# connector_board.net
KiCad netlist of a schematic drawn in EAGLE
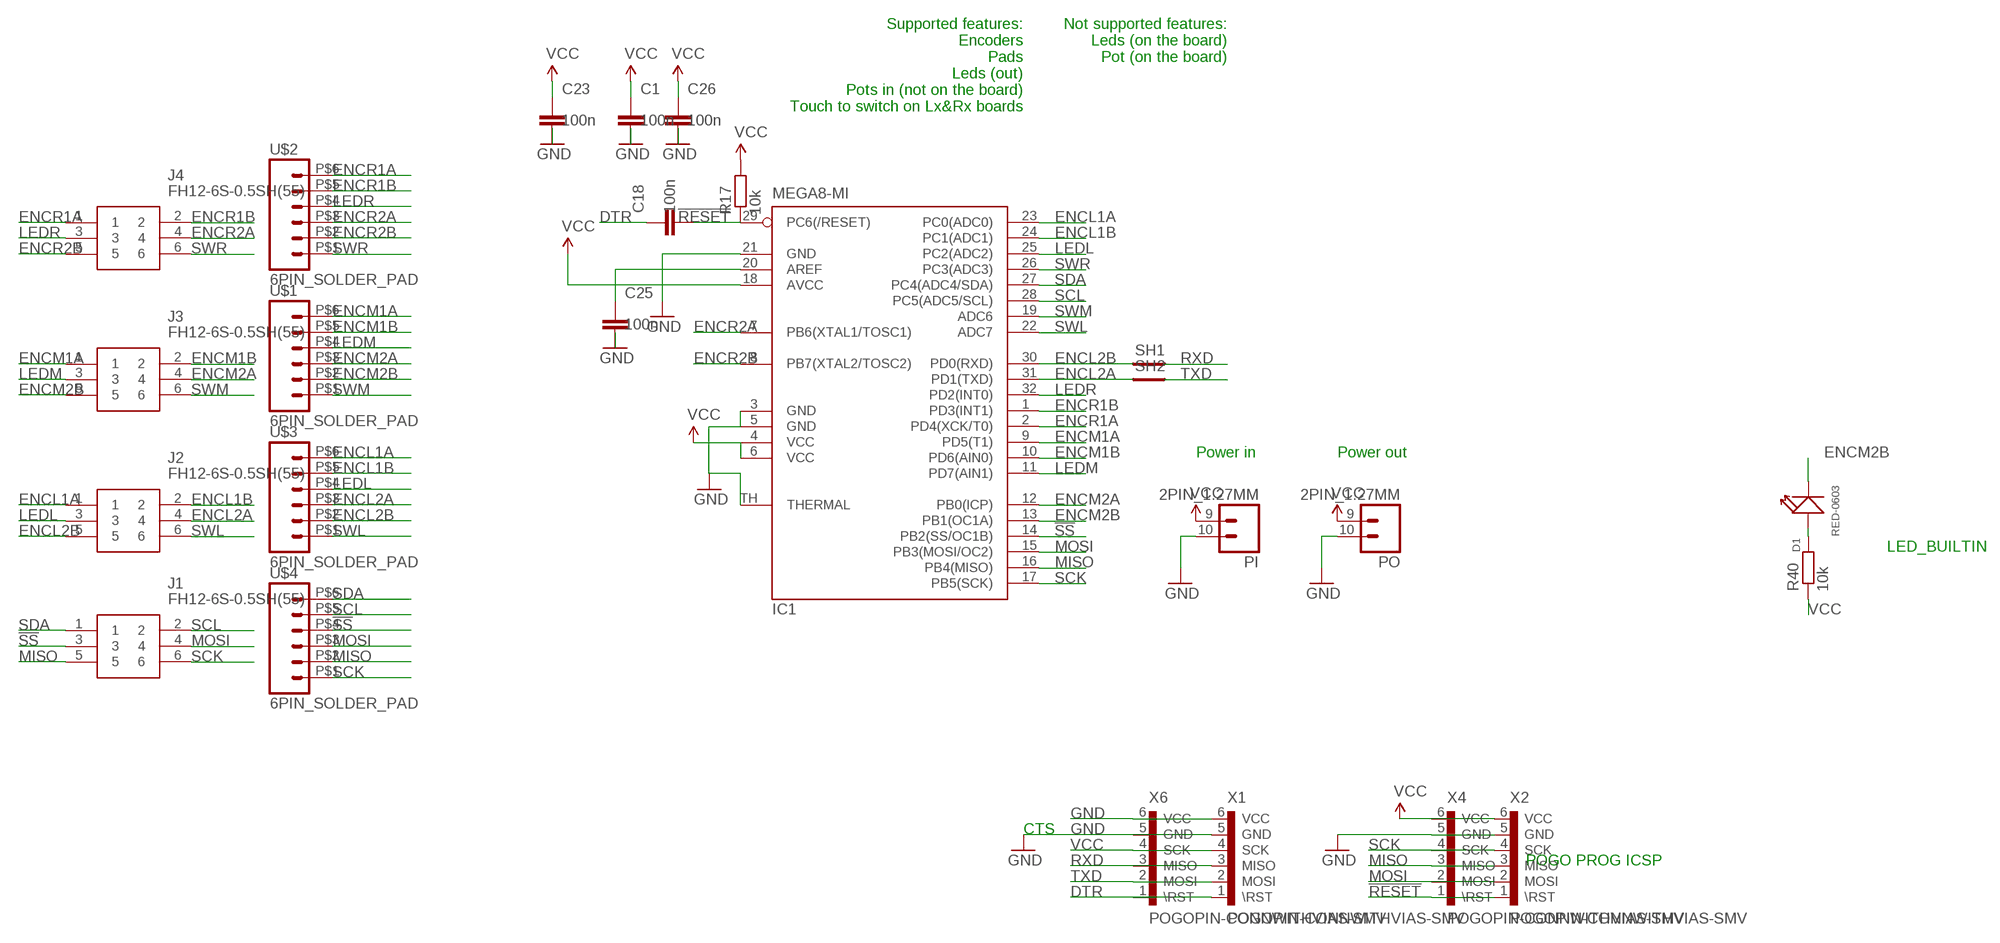
[diagram p0: schematic, sheet 1]
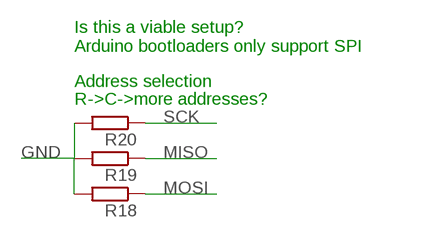
[diagram p1: schematic, sheet 2]

(export (version "E")
  (design (tool "Eeschema 10.0.6"))
  (components
    (comp (ref "C1")
      (value "100n")
      (footprint "eagle-import:C0603")
      (libsource (lib "eagle-import") (part "C-EUC0603"))
    )
    (comp (ref "C18")
      (value "100n")
      (footprint "eagle-import:C0603")
      (libsource (lib "eagle-import") (part "C-EUC0603"))
    )
    (comp (ref "C23")
      (value "100n")
      (footprint "eagle-import:C0603")
      (libsource (lib "eagle-import") (part "C-EUC0603"))
    )
    (comp (ref "C25")
      (value "100n")
      (footprint "eagle-import:C0603")
      (libsource (lib "eagle-import") (part "C-EUC0603"))
    )
    (comp (ref "C26")
      (value "100n")
      (footprint "eagle-import:C0603")
      (libsource (lib "eagle-import") (part "C-EUC0603"))
    )
    (comp (ref "D1")
      (value "RED-0603")
      (footprint "eagle-import:LED-0603")
      (fields (field (name "MPN") "19-217-R6C-AL1M2VY-3T"))
      (libsource (lib "eagle-import") (part "LED-SMD-RED-DIFFUSED(0603)"))
    )
    (comp (ref "IC1")
      (value "MEGA8-MI")
      (footprint "eagle-import:MLF32-TH")
      (fields (field (name "MPN") "ATMEGA88PA-MU"))
      (libsource (lib "eagle-import") (part "MEGA8-MI"))
    )
    (comp (ref "J1")
      (value "FH12-6S-0.5SH(55)")
      (footprint "eagle-import:FH12-6S-0.5SH(55)_1")
      (fields
        (field (name "MOUSER_PART_NUMBER") "798-FH12-6S-0.5SH55")
        (field (name "RS_PART_NUMBER") "7388811P")
      )
      (libsource (lib "eagle-import") (part "FH12-6S-0.5SH(55)"))
    )
    (comp (ref "J2")
      (value "FH12-6S-0.5SH(55)")
      (footprint "eagle-import:FH12-6S-0.5SH(55)_1")
      (fields
        (field (name "MOUSER_PART_NUMBER") "798-FH12-6S-0.5SH55")
        (field (name "RS_PART_NUMBER") "7388811P")
      )
      (libsource (lib "eagle-import") (part "FH12-6S-0.5SH(55)"))
    )
    (comp (ref "J3")
      (value "FH12-6S-0.5SH(55)")
      (footprint "eagle-import:FH12-6S-0.5SH(55)_1")
      (fields
        (field (name "MOUSER_PART_NUMBER") "798-FH12-6S-0.5SH55")
        (field (name "RS_PART_NUMBER") "7388811P")
      )
      (libsource (lib "eagle-import") (part "FH12-6S-0.5SH(55)"))
    )
    (comp (ref "J4")
      (value "FH12-6S-0.5SH(55)")
      (footprint "eagle-import:FH12-6S-0.5SH(55)_1")
      (fields
        (field (name "MOUSER_PART_NUMBER") "798-FH12-6S-0.5SH55")
        (field (name "RS_PART_NUMBER") "7388811P")
      )
      (libsource (lib "eagle-import") (part "FH12-6S-0.5SH(55)"))
    )
    (comp (ref "PI")
      (value "2PIN_1.27MM")
      (footprint "eagle-import:1X02_1.27MM_NO_SILK")
      (libsource (lib "eagle-import") (part "2PIN_1.27MM"))
    )
    (comp (ref "PO")
      (value "2PIN_1.27MM")
      (footprint "eagle-import:1X02_1.27MM_NO_SILK")
      (libsource (lib "eagle-import") (part "2PIN_1.27MM"))
    )
    (comp (ref "R17")
      (value "10k")
      (footprint "eagle-import:R0603")
      (libsource (lib "eagle-import") (part "R-EU_R0603"))
    )
    (comp (ref "R40")
      (value "10k")
      (footprint "eagle-import:R0603")
      (libsource (lib "eagle-import") (part "R-EU_R0603"))
    )
    (comp (ref "SH1")
      (value "SHORT")
      (footprint "eagle-import:SHORT_TOP_8MIL")
      (libsource (lib "eagle-import") (part "SHORT"))
    )
    (comp (ref "SH2")
      (value "SHORT")
      (footprint "eagle-import:SHORT_TOP_8MIL")
      (libsource (lib "eagle-import") (part "SHORT"))
    )
    (comp (ref "U$1")
      (value "6PIN_SOLDER_PAD")
      (footprint "eagle-import:6PIN_SOLDER_PAD")
      (libsource (lib "eagle-import") (part "6PIN_SOLDER_PAD"))
    )
    (comp (ref "U$2")
      (value "6PIN_SOLDER_PAD")
      (footprint "eagle-import:6PIN_SOLDER_PAD")
      (libsource (lib "eagle-import") (part "6PIN_SOLDER_PAD"))
    )
    (comp (ref "U$3")
      (value "6PIN_SOLDER_PAD")
      (footprint "eagle-import:6PIN_SOLDER_PAD")
      (libsource (lib "eagle-import") (part "6PIN_SOLDER_PAD"))
    )
    (comp (ref "U$4")
      (value "6PIN_SOLDER_PAD")
      (footprint "eagle-import:6PIN_SOLDER_PAD")
      (libsource (lib "eagle-import") (part "6PIN_SOLDER_PAD"))
    )
    (comp (ref "X1")
      (value "POGOPIN-CONNWITHVIAS-SMV")
      (footprint "eagle-import:POGOPROG-CONN-OH-SMALLERVIAS")
      (libsource (lib "eagle-import") (part "POGOPIN-CONNWITHVIAS-SMV"))
    )
    (comp (ref "X2")
      (value "POGOPIN-CONNWITHVIAS-SMV")
      (footprint "eagle-import:POGOPROG-CONN-OH-SMALLERVIAS")
      (libsource (lib "eagle-import") (part "POGOPIN-CONNWITHVIAS-SMV"))
    )
    (comp (ref "X4")
      (value "POGOPIN-CONNWITHVIAS-SMV")
      (footprint "eagle-import:POGOPROG-CONN-OH-SMALLERVIAS")
      (libsource (lib "eagle-import") (part "POGOPIN-CONNWITHVIAS-SMV"))
    )
    (comp (ref "X6")
      (value "POGOPIN-CONNWITHVIAS-SMV")
      (footprint "eagle-import:POGOPROG-CONN-OH-SMALLERVIAS")
      (libsource (lib "eagle-import") (part "POGOPIN-CONNWITHVIAS-SMV"))
    )
    (comp (ref "R18")
      (value "R-EU_R0603")
      (footprint "eagle-import:R0603")
      (libsource (lib "eagle-import") (part "R-EU_R0603"))
    )
    (comp (ref "R19")
      (value "R-EU_R0603")
      (footprint "eagle-import:R0603")
      (libsource (lib "eagle-import") (part "R-EU_R0603"))
    )
    (comp (ref "R20")
      (value "R-EU_R0603")
      (footprint "eagle-import:R0603")
      (libsource (lib "eagle-import") (part "R-EU_R0603"))
    )
  )
  (nets
    (net (code "1") (name "DTR") (class "Default")
      (node (ref "C18") (pin "1") (pinfunction "1_1") (pintype "passive"))
      (node (ref "X1") (pin "1") (pinfunction "\\RST_1") (pintype "bidirectional"))
      (node (ref "X6") (pin "1") (pinfunction "\\RST_1") (pintype "bidirectional"))
    )
    (net (code "2") (name "ENCL1A") (class "Default")
      (node (ref "IC1") (pin "23") (pinfunction "PC0(ADC0)_23") (pintype "bidirectional"))
      (node (ref "J2") (pin "1") (pinfunction "1_1") (pintype "bidirectional"))
      (node (ref "U$3") (pin "P$6") (pinfunction "6_P$6") (pintype "passive"))
    )
    (net (code "3") (name "ENCL1B") (class "Default")
      (node (ref "IC1") (pin "24") (pinfunction "PC1(ADC1)_24") (pintype "bidirectional"))
      (node (ref "J2") (pin "2") (pinfunction "2_2") (pintype "bidirectional"))
      (node (ref "U$3") (pin "P$5") (pinfunction "5_P$5") (pintype "passive"))
    )
    (net (code "4") (name "ENCL2A") (class "Default")
      (node (ref "IC1") (pin "31") (pinfunction "PD1(TXD)_31") (pintype "bidirectional"))
      (node (ref "J2") (pin "4") (pinfunction "4_4") (pintype "bidirectional"))
      (node (ref "SH2") (pin "P$1") (pinfunction "P$1_P$1") (pintype "bidirectional"))
      (node (ref "U$3") (pin "P$3") (pinfunction "3_P$3") (pintype "passive"))
    )
    (net (code "5") (name "ENCL2B") (class "Default")
      (node (ref "IC1") (pin "30") (pinfunction "PD0(RXD)_30") (pintype "bidirectional"))
      (node (ref "J2") (pin "5") (pinfunction "5_5") (pintype "bidirectional"))
      (node (ref "SH1") (pin "P$1") (pinfunction "P$1_P$1") (pintype "bidirectional"))
      (node (ref "U$3") (pin "P$2") (pinfunction "2_P$2") (pintype "passive"))
    )
    (net (code "6") (name "ENCM1A") (class "Default")
      (node (ref "IC1") (pin "9") (pinfunction "PD5(T1)_9") (pintype "bidirectional"))
      (node (ref "J3") (pin "1") (pinfunction "1_1") (pintype "bidirectional"))
      (node (ref "U$1") (pin "P$6") (pinfunction "6_P$6") (pintype "passive"))
    )
    (net (code "7") (name "ENCM1B") (class "Default")
      (node (ref "IC1") (pin "10") (pinfunction "PD6(AIN0)_10") (pintype "bidirectional"))
      (node (ref "J3") (pin "2") (pinfunction "2_2") (pintype "bidirectional"))
      (node (ref "U$1") (pin "P$5") (pinfunction "5_P$5") (pintype "passive"))
    )
    (net (code "8") (name "ENCM2A") (class "Default")
      (node (ref "IC1") (pin "12") (pinfunction "PB0(ICP)_12") (pintype "bidirectional"))
      (node (ref "J3") (pin "4") (pinfunction "4_4") (pintype "bidirectional"))
      (node (ref "U$1") (pin "P$3") (pinfunction "3_P$3") (pintype "passive"))
    )
    (net (code "9") (name "ENCM2B") (class "Default")
      (node (ref "D1") (pin "-") (pinfunction "-_-") (pintype "passive"))
      (node (ref "IC1") (pin "13") (pinfunction "PB1(OC1A)_13") (pintype "bidirectional"))
      (node (ref "J3") (pin "5") (pinfunction "5_5") (pintype "bidirectional"))
      (node (ref "U$1") (pin "P$2") (pinfunction "2_P$2") (pintype "passive"))
    )
    (net (code "10") (name "ENCR1A") (class "Default")
      (node (ref "IC1") (pin "2") (pinfunction "PD4(XCK/T0)_2") (pintype "bidirectional"))
      (node (ref "J4") (pin "1") (pinfunction "1_1") (pintype "bidirectional"))
      (node (ref "U$2") (pin "P$6") (pinfunction "6_P$6") (pintype "passive"))
    )
    (net (code "11") (name "ENCR1B") (class "Default")
      (node (ref "IC1") (pin "1") (pinfunction "PD3(INT1)_1") (pintype "bidirectional"))
      (node (ref "J4") (pin "2") (pinfunction "2_2") (pintype "bidirectional"))
      (node (ref "U$2") (pin "P$5") (pinfunction "5_P$5") (pintype "passive"))
    )
    (net (code "12") (name "ENCR2A") (class "Default")
      (node (ref "IC1") (pin "7") (pinfunction "PB6(XTAL1/TOSC1)_7") (pintype "bidirectional"))
      (node (ref "J4") (pin "4") (pinfunction "4_4") (pintype "bidirectional"))
      (node (ref "U$2") (pin "P$3") (pinfunction "3_P$3") (pintype "passive"))
    )
    (net (code "13") (name "ENCR2B") (class "Default")
      (node (ref "IC1") (pin "8") (pinfunction "PB7(XTAL2/TOSC2)_8") (pintype "bidirectional"))
      (node (ref "J4") (pin "5") (pinfunction "5_5") (pintype "bidirectional"))
      (node (ref "U$2") (pin "P$2") (pinfunction "2_P$2") (pintype "passive"))
    )
    (net (code "14") (name "GND") (class "Default")
      (node (ref "C1") (pin "2") (pinfunction "2_2") (pintype "passive"))
      (node (ref "C23") (pin "2") (pinfunction "2_2") (pintype "passive"))
      (node (ref "C25") (pin "2") (pinfunction "2_2") (pintype "passive"))
      (node (ref "C26") (pin "2") (pinfunction "2_2") (pintype "passive"))
      (node (ref "IC1") (pin "21") (pinfunction "GND_21") (pintype "power_in"))
      (node (ref "IC1") (pin "3") (pinfunction "GND_3") (pintype "power_in"))
      (node (ref "IC1") (pin "5") (pinfunction "GND_5") (pintype "power_in"))
      (node (ref "IC1") (pin "TH") (pinfunction "THERMAL_TH") (pintype "passive"))
      (node (ref "PI") (pin "10") (pinfunction "2_10") (pintype "passive"))
      (node (ref "PO") (pin "10") (pinfunction "2_10") (pintype "passive"))
      (node (ref "R18") (pin "2") (pinfunction "2_2") (pintype "passive"))
      (node (ref "R19") (pin "2") (pinfunction "2_2") (pintype "passive"))
      (node (ref "R20") (pin "2") (pinfunction "2_2") (pintype "passive"))
      (node (ref "X1") (pin "5") (pinfunction "GND_5") (pintype "bidirectional"))
      (node (ref "X1") (pin "6") (pinfunction "VCC_6") (pintype "bidirectional"))
      (node (ref "X2") (pin "5") (pinfunction "GND_5") (pintype "bidirectional"))
      (node (ref "X4") (pin "5") (pinfunction "GND_5") (pintype "bidirectional"))
      (node (ref "X6") (pin "5") (pinfunction "GND_5") (pintype "bidirectional"))
      (node (ref "X6") (pin "6") (pinfunction "VCC_6") (pintype "bidirectional"))
    )
    (net (code "15") (name "LEDL") (class "Default")
      (node (ref "IC1") (pin "25") (pinfunction "PC2(ADC2)_25") (pintype "bidirectional"))
      (node (ref "J2") (pin "3") (pinfunction "3_3") (pintype "bidirectional"))
      (node (ref "U$3") (pin "P$4") (pinfunction "4_P$4") (pintype "passive"))
    )
    (net (code "16") (name "LEDM") (class "Default")
      (node (ref "IC1") (pin "11") (pinfunction "PD7(AIN1)_11") (pintype "bidirectional"))
      (node (ref "J3") (pin "3") (pinfunction "3_3") (pintype "bidirectional"))
      (node (ref "U$1") (pin "P$4") (pinfunction "4_P$4") (pintype "passive"))
    )
    (net (code "17") (name "LEDR") (class "Default")
      (node (ref "IC1") (pin "32") (pinfunction "PD2(INT0)_32") (pintype "bidirectional"))
      (node (ref "J4") (pin "3") (pinfunction "3_3") (pintype "bidirectional"))
      (node (ref "U$2") (pin "P$4") (pinfunction "4_P$4") (pintype "passive"))
    )
    (net (code "18") (name "MISO") (class "Default")
      (node (ref "IC1") (pin "16") (pinfunction "PB4(MISO)_16") (pintype "bidirectional"))
      (node (ref "J1") (pin "5") (pinfunction "5_5") (pintype "bidirectional"))
      (node (ref "R19") (pin "1") (pinfunction "1_1") (pintype "passive"))
      (node (ref "U$4") (pin "P$2") (pinfunction "2_P$2") (pintype "passive"))
      (node (ref "X2") (pin "3") (pinfunction "MISO_3") (pintype "bidirectional"))
      (node (ref "X4") (pin "3") (pinfunction "MISO_3") (pintype "bidirectional"))
    )
    (net (code "19") (name "MOSI") (class "Default")
      (node (ref "IC1") (pin "15") (pinfunction "PB3(MOSI/OC2)_15") (pintype "bidirectional"))
      (node (ref "J1") (pin "4") (pinfunction "4_4") (pintype "bidirectional"))
      (node (ref "R18") (pin "1") (pinfunction "1_1") (pintype "passive"))
      (node (ref "U$4") (pin "P$3") (pinfunction "3_P$3") (pintype "passive"))
      (node (ref "X2") (pin "2") (pinfunction "MOSI_2") (pintype "bidirectional"))
      (node (ref "X4") (pin "2") (pinfunction "MOSI_2") (pintype "bidirectional"))
    )
    (net (code "20") (name "Net-(D1-Pad+)") (class "Default")
      (node (ref "D1") (pin "+") (pinfunction "+_+") (pintype "passive"))
      (node (ref "R40") (pin "2") (pinfunction "2_2") (pintype "passive"))
    )
    (net (code "21") (name "Net-(IC1-AREF)") (class "Default")
      (node (ref "C25") (pin "1") (pinfunction "1_1") (pintype "passive"))
      (node (ref "IC1") (pin "20") (pinfunction "AREF_20") (pintype "passive"))
    )
    (net (code "22") (name "RXD") (class "Default")
      (node (ref "SH1") (pin "P$2") (pinfunction "P$2_P$2") (pintype "bidirectional"))
      (node (ref "X1") (pin "3") (pinfunction "MISO_3") (pintype "bidirectional"))
      (node (ref "X6") (pin "3") (pinfunction "MISO_3") (pintype "bidirectional"))
    )
    (net (code "23") (name "SCK") (class "Default")
      (node (ref "IC1") (pin "17") (pinfunction "PB5(SCK)_17") (pintype "bidirectional"))
      (node (ref "J1") (pin "6") (pinfunction "6_6") (pintype "bidirectional"))
      (node (ref "R20") (pin "1") (pinfunction "1_1") (pintype "passive"))
      (node (ref "U$4") (pin "P$1") (pinfunction "1_P$1") (pintype "passive"))
      (node (ref "X2") (pin "4") (pinfunction "SCK_4") (pintype "bidirectional"))
      (node (ref "X4") (pin "4") (pinfunction "SCK_4") (pintype "bidirectional"))
    )
    (net (code "24") (name "SCL") (class "Default")
      (node (ref "IC1") (pin "28") (pinfunction "PC5(ADC5/SCL)_28") (pintype "bidirectional"))
      (node (ref "J1") (pin "2") (pinfunction "2_2") (pintype "bidirectional"))
      (node (ref "U$4") (pin "P$5") (pinfunction "5_P$5") (pintype "passive"))
    )
    (net (code "25") (name "SDA") (class "Default")
      (node (ref "IC1") (pin "27") (pinfunction "PC4(ADC4/SDA)_27") (pintype "bidirectional"))
      (node (ref "J1") (pin "1") (pinfunction "1_1") (pintype "bidirectional"))
      (node (ref "U$4") (pin "P$6") (pinfunction "6_P$6") (pintype "passive"))
    )
    (net (code "26") (name "SWL") (class "Default")
      (node (ref "IC1") (pin "22") (pinfunction "ADC7_22") (pintype "bidirectional"))
      (node (ref "J2") (pin "6") (pinfunction "6_6") (pintype "bidirectional"))
      (node (ref "U$3") (pin "P$1") (pinfunction "1_P$1") (pintype "passive"))
    )
    (net (code "27") (name "SWM") (class "Default")
      (node (ref "IC1") (pin "19") (pinfunction "ADC6_19") (pintype "bidirectional"))
      (node (ref "J3") (pin "6") (pinfunction "6_6") (pintype "bidirectional"))
      (node (ref "U$1") (pin "P$1") (pinfunction "1_P$1") (pintype "passive"))
    )
    (net (code "28") (name "SWR") (class "Default")
      (node (ref "IC1") (pin "26") (pinfunction "PC3(ADC3)_26") (pintype "bidirectional"))
      (node (ref "J4") (pin "6") (pinfunction "6_6") (pintype "bidirectional"))
      (node (ref "U$2") (pin "P$1") (pinfunction "1_P$1") (pintype "passive"))
    )
    (net (code "29") (name "TXD") (class "Default")
      (node (ref "SH2") (pin "P$2") (pinfunction "P$2_P$2") (pintype "bidirectional"))
      (node (ref "X1") (pin "2") (pinfunction "MOSI_2") (pintype "bidirectional"))
      (node (ref "X6") (pin "2") (pinfunction "MOSI_2") (pintype "bidirectional"))
    )
    (net (code "30") (name "VCC") (class "Default")
      (node (ref "C1") (pin "1") (pinfunction "1_1") (pintype "passive"))
      (node (ref "C23") (pin "1") (pinfunction "1_1") (pintype "passive"))
      (node (ref "C26") (pin "1") (pinfunction "1_1") (pintype "passive"))
      (node (ref "IC1") (pin "18") (pinfunction "AVCC_18") (pintype "power_in"))
      (node (ref "IC1") (pin "4") (pinfunction "VCC_4") (pintype "power_in"))
      (node (ref "IC1") (pin "6") (pinfunction "VCC_6") (pintype "power_in"))
      (node (ref "PI") (pin "9") (pinfunction "1_9") (pintype "passive"))
      (node (ref "PO") (pin "9") (pinfunction "1_9") (pintype "passive"))
      (node (ref "R17") (pin "2") (pinfunction "2_2") (pintype "passive"))
      (node (ref "R40") (pin "1") (pinfunction "1_1") (pintype "passive"))
      (node (ref "X1") (pin "4") (pinfunction "SCK_4") (pintype "bidirectional"))
      (node (ref "X2") (pin "6") (pinfunction "VCC_6") (pintype "bidirectional"))
      (node (ref "X4") (pin "6") (pinfunction "VCC_6") (pintype "bidirectional"))
      (node (ref "X6") (pin "4") (pinfunction "SCK_4") (pintype "bidirectional"))
    )
    (net (code "31") (name "~{RESET}") (class "Default")
      (node (ref "C18") (pin "2") (pinfunction "2_2") (pintype "passive"))
      (node (ref "IC1") (pin "29") (pinfunction "PC6(/RESET)_29") (pintype "bidirectional"))
      (node (ref "R17") (pin "1") (pinfunction "1_1") (pintype "passive"))
      (node (ref "X2") (pin "1") (pinfunction "\\RST_1") (pintype "bidirectional"))
      (node (ref "X4") (pin "1") (pinfunction "\\RST_1") (pintype "bidirectional"))
    )
    (net (code "32") (name "~{SS}") (class "Default")
      (node (ref "IC1") (pin "14") (pinfunction "PB2(SS/OC1B)_14") (pintype "bidirectional"))
      (node (ref "J1") (pin "3") (pinfunction "3_3") (pintype "bidirectional"))
      (node (ref "U$4") (pin "P$4") (pinfunction "4_P$4") (pintype "passive"))
    )
  )
)
